# 7_-_MIO0_MIO1_SD_USB.net
KiCad netlist of a schematic drawn in Altium Designer
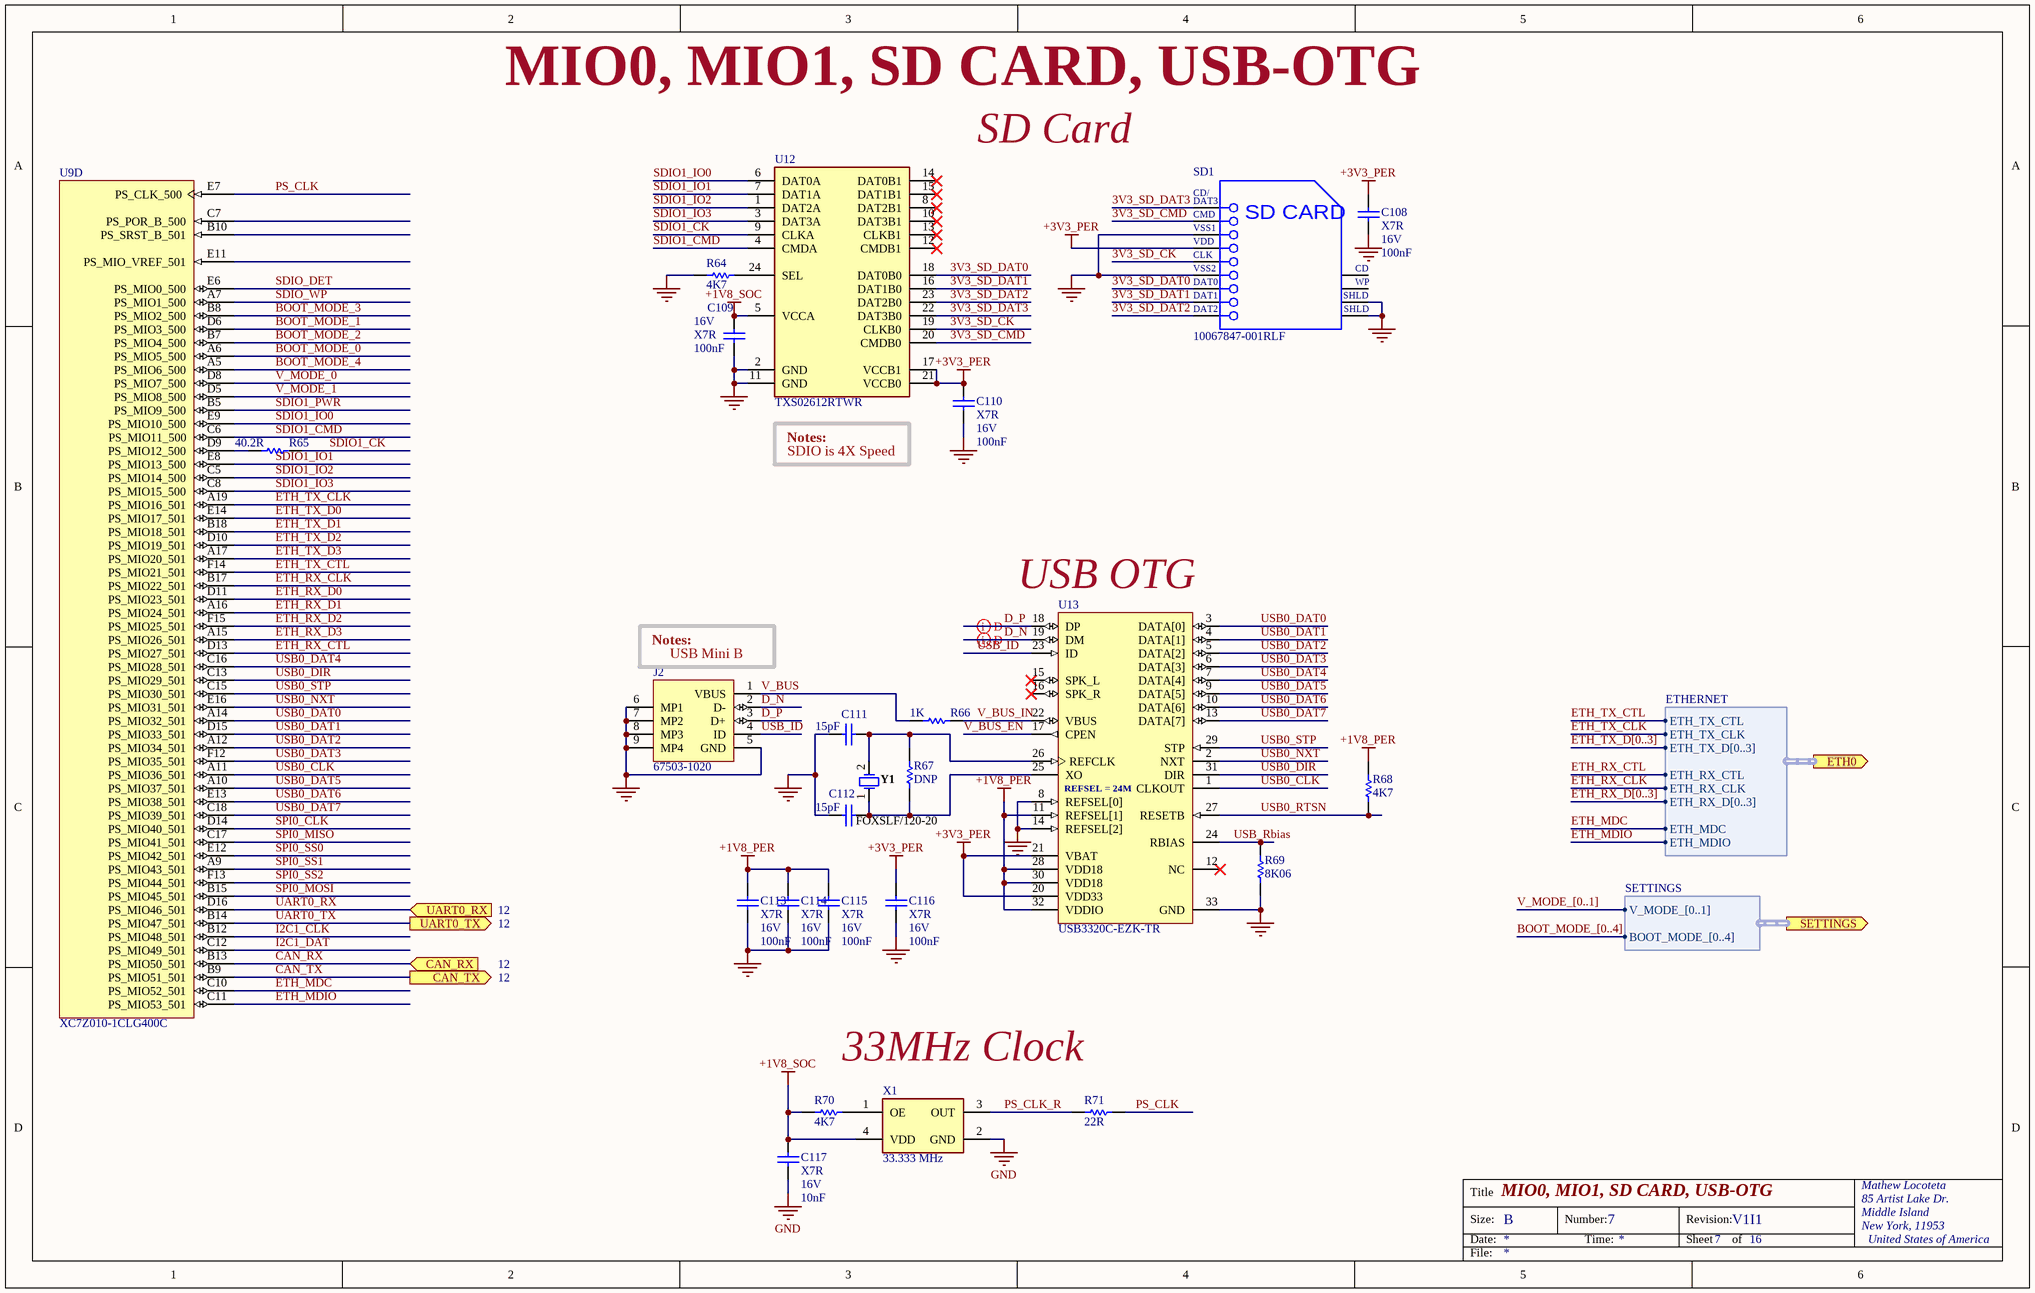
[diagram p0: [7] - MIO0, MIO1, SD, USB.SchDoc]

(export (version "E")
  (design (tool "Eeschema 10.0.6"))
  (components
    (comp (ref "C108")
      (value "100nF 0402 16V")
      (fields
        (field (name "MANUFACTURER") "KEMET")
        (field (name "MANUFACTURER PART NUMBER") "C0402C104J4RACTU")
        (field (name "TOLERANCE") "5%")
        (field (name "DIELECTRIC") "X7R")
        (field (name "VOLTAGE RATING") "16V")
        (field (name "CAPACITANCE") "100nF")
      )
      (libsource (lib "Zynq 7000") (part "C0402C104J4RACTU"))
    )
    (comp (ref "C109")
      (value "100nF 0402 16V")
      (fields
        (field (name "MANUFACTURER") "KEMET")
        (field (name "MANUFACTURER PART NUMBER") "C0402C104J4RACTU")
        (field (name "TOLERANCE") "5%")
        (field (name "DIELECTRIC") "X7R")
        (field (name "VOLTAGE RATING") "16V")
        (field (name "CAPACITANCE") "100nF")
      )
      (libsource (lib "Zynq 7000") (part "C0402C104J4RACTU"))
    )
    (comp (ref "C110")
      (value "100nF 0402 16V")
      (fields
        (field (name "MANUFACTURER") "KEMET")
        (field (name "MANUFACTURER PART NUMBER") "C0402C104J4RACTU")
        (field (name "TOLERANCE") "5%")
        (field (name "DIELECTRIC") "X7R")
        (field (name "VOLTAGE RATING") "16V")
        (field (name "CAPACITANCE") "100nF")
      )
      (libsource (lib "Zynq 7000") (part "C0402C104J4RACTU"))
    )
    (comp (ref "C111")
      (value "15 pF 50V C0G")
      (description "CAP CER 15PF 50V C0G 0402")
      (fields
        (field (name "MANUFACTURER") "TDK")
        (field (name "MANUFACTURER PART NUMBER") "CGA2B2C0G1H150J050BA")
        (field (name "CAPACITANCE") "15pF")
      )
      (libsource (lib "Zynq 7000") (part "CGA2B2C0G1H150J050BA"))
    )
    (comp (ref "C112")
      (value "15 pF 50V C0G")
      (description "CAP CER 15PF 50V C0G 0402")
      (fields
        (field (name "MANUFACTURER") "TDK")
        (field (name "MANUFACTURER PART NUMBER") "CGA2B2C0G1H150J050BA")
        (field (name "CAPACITANCE") "15pF")
      )
      (libsource (lib "Zynq 7000") (part "CGA2B2C0G1H150J050BA"))
    )
    (comp (ref "C113")
      (value "100nF 0402 16V")
      (fields
        (field (name "MANUFACTURER") "KEMET")
        (field (name "MANUFACTURER PART NUMBER") "C0402C104J4RACTU")
        (field (name "TOLERANCE") "5%")
        (field (name "DIELECTRIC") "X7R")
        (field (name "VOLTAGE RATING") "16V")
        (field (name "CAPACITANCE") "100nF")
      )
      (libsource (lib "Zynq 7000") (part "C0402C104J4RACTU"))
    )
    (comp (ref "C114")
      (value "100nF 0402 16V")
      (fields
        (field (name "MANUFACTURER") "KEMET")
        (field (name "MANUFACTURER PART NUMBER") "C0402C104J4RACTU")
        (field (name "TOLERANCE") "5%")
        (field (name "DIELECTRIC") "X7R")
        (field (name "VOLTAGE RATING") "16V")
        (field (name "CAPACITANCE") "100nF")
      )
      (libsource (lib "Zynq 7000") (part "C0402C104J4RACTU"))
    )
    (comp (ref "C115")
      (value "100nF 0402 16V")
      (fields
        (field (name "MANUFACTURER") "KEMET")
        (field (name "MANUFACTURER PART NUMBER") "C0402C104J4RACTU")
        (field (name "TOLERANCE") "5%")
        (field (name "DIELECTRIC") "X7R")
        (field (name "VOLTAGE RATING") "16V")
        (field (name "CAPACITANCE") "100nF")
      )
      (libsource (lib "Zynq 7000") (part "C0402C104J4RACTU"))
    )
    (comp (ref "C116")
      (value "100nF 0402 16V")
      (fields
        (field (name "MANUFACTURER") "KEMET")
        (field (name "MANUFACTURER PART NUMBER") "C0402C104J4RACTU")
        (field (name "TOLERANCE") "5%")
        (field (name "DIELECTRIC") "X7R")
        (field (name "VOLTAGE RATING") "16V")
        (field (name "CAPACITANCE") "100nF")
      )
      (libsource (lib "Zynq 7000") (part "C0402C104J4RACTU"))
    )
    (comp (ref "C117")
      (value "10nF 16V 0402 X7R")
      (fields
        (field (name "MANUFACTURER") "KEMET")
        (field (name "MANUFACTURER PART NUMBER") "C0402C103J4RACTU")
        (field (name "TOLERANCE") "5%")
        (field (name "DIELECTRIC") "X7R")
        (field (name "VOLTAGE RATING") "16V")
        (field (name "CAPACITANCE") "10nF")
      )
      (libsource (lib "Zynq 7000") (part "C0402C103J4RACTU"))
    )
    (comp (ref "J2")
      (value "67503-1020")
      (footprint "MOLX-67503-1020_V")
      (description "USB, MINI, SMD, RA KME04-USBMU03A01")
      (fields (field (name "MANUFACTURER") "Molex"))
      (libsource (lib "Altium Content Vault") (part "MOLX-67503-1020"))
    )
    (comp (ref "R64")
      (value "4K7 0402 1%")
      (description "Resistor SMD 4.7 kOhm 0402 PU=10000 ST, CRCW04024K70FKED, Vishay")
      (fields
        (field (name "MANUFACTURER") "Vishay")
        (field (name "MANUFACTURER PART NUMBER") "CRCW04024K70FKED")
        (field (name "RESISTANCE") "4K7")
      )
      (libsource (lib "Zynq 7000") (part "CRCW04024K70FKED"))
    )
    (comp (ref "R65")
      (value "40R2 1% 0402")
      (description "RES SMD 40.2 OHM 1% 1/16W 0402")
      (fields
        (field (name "MANUFACTURER") "Vishay")
        (field (name "MANUFACTURER PART NUMBER") "CRCW040240R2FKED")
        (field (name "RESISTANCE") "40.2R")
      )
      (libsource (lib "Zynq 7000") (part "CRCW040240R2FKED"))
    )
    (comp (ref "R66")
      (value "1K 1/8W 0402 1%")
      (description "Res Thick Film 0402 1K Ohm 1% 1/8W 100ppm/C Molded SMD SMD Paper T/R")
      (fields
        (field (name "MANUFACTURER") "Vishay Dale")
        (field (name "MANUFACTURER PART NUMBER") "CRCW04021K00FKEDHP")
        (field (name "RESISTANCE") "1K")
      )
      (libsource (lib "Zynq 7000") (part "CRCW04021K00FKEDHP"))
    )
    (comp (ref "R67")
      (value "DNP")
      (fields
        (field (name "MANUFACTURER") "Vishay")
        (field (name "MANUFACTURER PART NUMBER") "CRCW04024K70FKED")
        (field (name "TOLERANCE") "1%")
        (field (name "RESISTANCE") "DNP")
      )
      (libsource (lib "Zynq 7000") (part "CRCW04024K70FKED"))
    )
    (comp (ref "R68")
      (value "4K7 0402 1%")
      (description "Resistor SMD 4.7 kOhm 0402 PU=10000 ST, CRCW04024K70FKED, Vishay")
      (fields
        (field (name "MANUFACTURER") "Vishay")
        (field (name "MANUFACTURER PART NUMBER") "CRCW04024K70FKED")
        (field (name "RESISTANCE") "4K7")
      )
      (libsource (lib "Zynq 7000") (part "CRCW04024K70FKED"))
    )
    (comp (ref "R69")
      (value "8K06 0402 1%")
      (description "Res Thick Film 0402 8.06K Ohm 1% 0.063W(1/16W) ±100ppm/C Molded SMD Automotive Paper T/R")
      (fields
        (field (name "MANUFACTURER") "Vishay")
        (field (name "MANUFACTURER PART NUMBER") "CRCW04028K06FKED")
        (field (name "RESISTANCE") "8K06")
      )
      (libsource (lib "Zynq 7000") (part "CRCW04028K06FKED"))
    )
    (comp (ref "R70")
      (value "4K7 0402 1%")
      (description "Resistor SMD 4.7 kOhm 0402 PU=10000 ST, CRCW04024K70FKED, Vishay")
      (fields
        (field (name "MANUFACTURER") "Vishay")
        (field (name "MANUFACTURER PART NUMBER") "CRCW04024K70FKED")
        (field (name "RESISTANCE") "4K7")
      )
      (libsource (lib "Zynq 7000") (part "CRCW04024K70FKED"))
    )
    (comp (ref "R71")
      (value "22R 0402 1%")
      (description "VISHAY - CRCW040222R0FKED. - Resistor Case Style:0402 [1005 Metric]")
      (fields
        (field (name "MANUFACTURER") "Vishay")
        (field (name "MANUFACTURER PART NUMBER") "CRCW040222R0FKED")
        (field (name "RESISTANCE") "22R")
      )
      (libsource (lib "Zynq 7000") (part "CRCW040222R0FKED"))
    )
    (comp (ref "SD1")
      (value "10067847-001RLF")
      (footprint "FCI-10067847-001RLF_V")
      (description "Assembly SD Card Reader, Famale, 11 Way, -40 to 105 degC, RoHS, Tape and Reel")
      (fields (field (name "MANUFACTURER") "FCI Electronics"))
      (libsource (lib "Altium Content Vault") (part "CN-SD-9-2SW-2S"))
    )
    (comp (ref "U9")
      (value "XC7Z010-1CLG400C")
      (footprint "CLG400")
      (fields (field (name "GENERIC PART NUMBER") "XC7Z010"))
      (libsource (lib "Altium Content Vault") (part "XNLX-XC7Z010-CLG400"))
    )
    (comp (ref "U12")
      (value "TXS02612RTWR")
      (description "TEXAS INSTRUMENTS - TXS02612RTWR - SDIO EXPANDER W/VOLT TRANSLATOR, WQFN-24")
      (fields (field (name "MANUFACTURER") "Texas Instruments"))
      (libsource (lib "Zynq 7000") (part "TXS02612RTWR"))
    )
    (comp (ref "U13")
      (value "USB3320C-EZK-TR")
      (footprint "MCHP-QFN-32-5x5_V2")
      (fields (field (name "MANUFACTURER") "Microchip"))
      (libsource (lib "Altium Content Vault") (part "MCHP-USB3320-32"))
    )
    (comp (ref "X1")
      (value "33.333 MHz")
      (description "OSC MEMS 33.333MHZ CMOS SMD")
      (fields
        (field (name "MANUFACTURER") "Abracon")
        (field (name "MANUFACTURER PART NUMBER") "ASVMB-33.333MHZ-LY-T")
      )
      (libsource (lib "Zynq 7000") (part "ASVMB-33.333MHZ-LY-T"))
    )
    (comp (ref "Y1")
      (value "FOXSLF/120-20")
      (footprint "FOX-FOXSLF-2_V")
      (description "Resistance Weld Thru-Hole Crystal, 12 MHz, +/-30 ppm, -20 to 70 degC, 2-Pin THD, RoHS, Bulk")
      (libsource (lib "Altium Content Vault") (part "XTAL-1-2-2"))
    )
  )
  (nets
    (net (code "3") (name "+1V8_PER") (class "Default")
      (node (ref "C113") (pin "2") (pinfunction "2_2") (pintype "passive"))
      (node (ref "C114") (pin "2") (pinfunction "2_2") (pintype "passive"))
      (node (ref "C115") (pin "2") (pinfunction "2_2") (pintype "passive"))
      (node (ref "R68") (pin "2") (pinfunction "2_2") (pintype "passive"))
      (node (ref "U13") (pin "11") (pinfunction "REFSEL[1]_11") (pintype "input"))
      (node (ref "U13") (pin "28") (pinfunction "VDD18_28") (pintype "power_in"))
      (node (ref "U13") (pin "30") (pinfunction "VDD18_30") (pintype "power_in"))
      (node (ref "U13") (pin "32") (pinfunction "VDDIO_32") (pintype "power_in"))
    )
    (net (code "4") (name "+1V8_SOC") (class "Default")
      (node (ref "C109") (pin "2") (pinfunction "2_2") (pintype "passive"))
      (node (ref "C117") (pin "2") (pinfunction "2_2") (pintype "passive"))
      (node (ref "R70") (pin "1") (pinfunction "1_1") (pintype "passive"))
      (node (ref "U12") (pin "5") (pinfunction "VCCA_5") (pintype "passive"))
      (node (ref "X1") (pin "4") (pinfunction "VDD_4") (pintype "passive"))
    )
    (net (code "5") (name "+3V3_PER") (class "Default")
      (node (ref "C108") (pin "1") (pinfunction "1_1") (pintype "passive"))
      (node (ref "C110") (pin "1") (pinfunction "1_1") (pintype "passive"))
      (node (ref "C116") (pin "2") (pinfunction "2_2") (pintype "passive"))
      (node (ref "SD1") (pin "4") (pinfunction "VDD_4") (pintype "passive"))
      (node (ref "U12") (pin "17") (pinfunction "VCCB1_17") (pintype "passive"))
      (node (ref "U12") (pin "21") (pinfunction "VCCB0_21") (pintype "passive"))
      (node (ref "U13") (pin "20") (pinfunction "VDD33_20") (pintype "power_in"))
      (node (ref "U13") (pin "21") (pinfunction "VBAT_21") (pintype "power_in"))
    )
    (net (code "6") (name "/3V3_SD_CK") (class "Default")
      (node (ref "SD1") (pin "5") (pinfunction "CLK_5") (pintype "passive"))
      (node (ref "U12") (pin "19") (pinfunction "CLKB0_19") (pintype "passive"))
    )
    (net (code "7") (name "/3V3_SD_CMD") (class "Default")
      (node (ref "SD1") (pin "2") (pinfunction "CMD_2") (pintype "passive"))
      (node (ref "U12") (pin "20") (pinfunction "CMDB0_20") (pintype "passive"))
    )
    (net (code "8") (name "/3V3_SD_DAT0") (class "Default")
      (node (ref "SD1") (pin "7") (pinfunction "DAT0_7") (pintype "passive"))
      (node (ref "U12") (pin "18") (pinfunction "DAT0B0_18") (pintype "passive"))
    )
    (net (code "9") (name "/3V3_SD_DAT1") (class "Default")
      (node (ref "SD1") (pin "8") (pinfunction "DAT1_8") (pintype "passive"))
      (node (ref "U12") (pin "16") (pinfunction "DAT1B0_16") (pintype "passive"))
    )
    (net (code "10") (name "/3V3_SD_DAT2") (class "Default")
      (node (ref "SD1") (pin "9") (pinfunction "DAT2_9") (pintype "passive"))
      (node (ref "U12") (pin "23") (pinfunction "DAT2B0_23") (pintype "passive"))
    )
    (net (code "11") (name "/3V3_SD_DAT3") (class "Default")
      (node (ref "SD1") (pin "1") (pinfunction "CD/DAT3_1") (pintype "passive"))
      (node (ref "U12") (pin "22") (pinfunction "DAT3B0_22") (pintype "passive"))
    )
    (net (code "12") (name "/BOOT_MODE_0") (class "Default")
      (node (ref "U9") (pin "A6") (pinfunction "PS_MIO5_500_A6") (pintype "bidirectional"))
    )
    (net (code "13") (name "/BOOT_MODE_1") (class "Default")
      (node (ref "U9") (pin "D6") (pinfunction "PS_MIO3_500_D6") (pintype "bidirectional"))
    )
    (net (code "14") (name "/BOOT_MODE_2") (class "Default")
      (node (ref "U9") (pin "B7") (pinfunction "PS_MIO4_500_B7") (pintype "bidirectional"))
    )
    (net (code "15") (name "/BOOT_MODE_3") (class "Default")
      (node (ref "U9") (pin "B8") (pinfunction "PS_MIO2_500_B8") (pintype "bidirectional"))
    )
    (net (code "16") (name "/BOOT_MODE_4") (class "Default")
      (node (ref "U9") (pin "A5") (pinfunction "PS_MIO6_500_A5") (pintype "bidirectional"))
    )
    (net (code "17") (name "/CAN_RX") (class "Default")
      (node (ref "U9") (pin "B13") (pinfunction "PS_MIO50_501_B13") (pintype "bidirectional"))
    )
    (net (code "18") (name "/CAN_TX") (class "Default")
      (node (ref "U9") (pin "B9") (pinfunction "PS_MIO51_501_B9") (pintype "bidirectional"))
    )
    (net (code "19") (name "/D_N") (class "Default")
      (node (ref "J2") (pin "2") (pinfunction "D-_2") (pintype "bidirectional"))
      (node (ref "U13") (pin "19") (pinfunction "DM_19") (pintype "bidirectional"))
    )
    (net (code "20") (name "/D_P") (class "Default")
      (node (ref "J2") (pin "3") (pinfunction "D+_3") (pintype "bidirectional"))
      (node (ref "U13") (pin "18") (pinfunction "DP_18") (pintype "bidirectional"))
    )
    (net (code "22") (name "/ETH_MDC") (class "Default")
      (node (ref "U9") (pin "C10") (pinfunction "PS_MIO52_501_C10") (pintype "bidirectional"))
    )
    (net (code "23") (name "/ETH_MDIO") (class "Default")
      (node (ref "U9") (pin "C11") (pinfunction "PS_MIO53_501_C11") (pintype "bidirectional"))
    )
    (net (code "24") (name "/ETH_RX_CLK") (class "Default")
      (node (ref "U9") (pin "B17") (pinfunction "PS_MIO22_501_B17") (pintype "bidirectional"))
    )
    (net (code "25") (name "/ETH_RX_CTL") (class "Default")
      (node (ref "U9") (pin "D13") (pinfunction "PS_MIO27_501_D13") (pintype "bidirectional"))
    )
    (net (code "26") (name "/ETH_RX_D0") (class "Default")
      (node (ref "U9") (pin "D11") (pinfunction "PS_MIO23_501_D11") (pintype "bidirectional"))
    )
    (net (code "27") (name "/ETH_RX_D1") (class "Default")
      (node (ref "U9") (pin "A16") (pinfunction "PS_MIO24_501_A16") (pintype "bidirectional"))
    )
    (net (code "28") (name "/ETH_RX_D2") (class "Default")
      (node (ref "U9") (pin "F15") (pinfunction "PS_MIO25_501_F15") (pintype "bidirectional"))
    )
    (net (code "29") (name "/ETH_RX_D3") (class "Default")
      (node (ref "U9") (pin "A15") (pinfunction "PS_MIO26_501_A15") (pintype "bidirectional"))
    )
    (net (code "31") (name "/ETH_TX_CLK") (class "Default")
      (node (ref "U9") (pin "A19") (pinfunction "PS_MIO16_501_A19") (pintype "bidirectional"))
    )
    (net (code "32") (name "/ETH_TX_CTL") (class "Default")
      (node (ref "U9") (pin "F14") (pinfunction "PS_MIO21_501_F14") (pintype "bidirectional"))
    )
    (net (code "33") (name "/ETH_TX_D0") (class "Default")
      (node (ref "U9") (pin "E14") (pinfunction "PS_MIO17_501_E14") (pintype "bidirectional"))
    )
    (net (code "34") (name "/ETH_TX_D1") (class "Default")
      (node (ref "U9") (pin "B18") (pinfunction "PS_MIO18_501_B18") (pintype "bidirectional"))
    )
    (net (code "35") (name "/ETH_TX_D2") (class "Default")
      (node (ref "U9") (pin "D10") (pinfunction "PS_MIO19_501_D10") (pintype "bidirectional"))
    )
    (net (code "36") (name "/ETH_TX_D3") (class "Default")
      (node (ref "U9") (pin "A17") (pinfunction "PS_MIO20_501_A17") (pintype "bidirectional"))
    )
    (net (code "37") (name "/I2C1_CLK") (class "Default")
      (node (ref "U9") (pin "B12") (pinfunction "PS_MIO48_501_B12") (pintype "bidirectional"))
    )
    (net (code "38") (name "/I2C1_DAT") (class "Default")
      (node (ref "U9") (pin "C12") (pinfunction "PS_MIO49_501_C12") (pintype "bidirectional"))
    )
    (net (code "39") (name "/PS_CLK") (class "Default")
      (node (ref "R71") (pin "2") (pinfunction "2_2") (pintype "passive"))
      (node (ref "U9") (pin "E7") (pinfunction "PS_CLK_500_E7") (pintype "input"))
    )
    (net (code "40") (name "/PS_CLK_R") (class "Default")
      (node (ref "R71") (pin "1") (pinfunction "1_1") (pintype "passive"))
      (node (ref "X1") (pin "3") (pinfunction "OUT_3") (pintype "passive"))
    )
    (net (code "41") (name "/SDIO1_CK") (class "Default")
      (node (ref "R65") (pin "2") (pinfunction "2_2") (pintype "passive"))
      (node (ref "U12") (pin "9") (pinfunction "CLKA_9") (pintype "passive"))
    )
    (net (code "42") (name "/SDIO1_CMD") (class "Default")
      (node (ref "U12") (pin "4") (pinfunction "CMDA_4") (pintype "passive"))
      (node (ref "U9") (pin "C6") (pinfunction "PS_MIO11_500_C6") (pintype "bidirectional"))
    )
    (net (code "43") (name "/SDIO1_IO0") (class "Default")
      (node (ref "U12") (pin "6") (pinfunction "DAT0A_6") (pintype "passive"))
      (node (ref "U9") (pin "E9") (pinfunction "PS_MIO10_500_E9") (pintype "bidirectional"))
    )
    (net (code "44") (name "/SDIO1_IO1") (class "Default")
      (node (ref "U12") (pin "7") (pinfunction "DAT1A_7") (pintype "passive"))
      (node (ref "U9") (pin "E8") (pinfunction "PS_MIO13_500_E8") (pintype "bidirectional"))
    )
    (net (code "45") (name "/SDIO1_IO2") (class "Default")
      (node (ref "U12") (pin "1") (pinfunction "DAT2A_1") (pintype "passive"))
      (node (ref "U9") (pin "C5") (pinfunction "PS_MIO14_500_C5") (pintype "bidirectional"))
    )
    (net (code "46") (name "/SDIO1_IO3") (class "Default")
      (node (ref "U12") (pin "3") (pinfunction "DAT3A_3") (pintype "passive"))
      (node (ref "U9") (pin "C8") (pinfunction "PS_MIO15_500_C8") (pintype "bidirectional"))
    )
    (net (code "47") (name "/SDIO1_PWR") (class "Default")
      (node (ref "U9") (pin "B5") (pinfunction "PS_MIO9_500_B5") (pintype "bidirectional"))
    )
    (net (code "48") (name "/SDIO_DET") (class "Default")
      (node (ref "U9") (pin "E6") (pinfunction "PS_MIO0_500_E6") (pintype "bidirectional"))
    )
    (net (code "49") (name "/SDIO_WP") (class "Default")
      (node (ref "U9") (pin "A7") (pinfunction "PS_MIO1_500_A7") (pintype "bidirectional"))
    )
    (net (code "51") (name "/SPI0_CLK") (class "Default")
      (node (ref "U9") (pin "D14") (pinfunction "PS_MIO40_501_D14") (pintype "bidirectional"))
    )
    (net (code "52") (name "/SPI0_MISO") (class "Default")
      (node (ref "U9") (pin "C17") (pinfunction "PS_MIO41_501_C17") (pintype "bidirectional"))
    )
    (net (code "53") (name "/SPI0_MOSI") (class "Default")
      (node (ref "U9") (pin "B15") (pinfunction "PS_MIO45_501_B15") (pintype "bidirectional"))
    )
    (net (code "54") (name "/SPI0_SS0") (class "Default")
      (node (ref "U9") (pin "E12") (pinfunction "PS_MIO42_501_E12") (pintype "bidirectional"))
    )
    (net (code "55") (name "/SPI0_SS1") (class "Default")
      (node (ref "U9") (pin "A9") (pinfunction "PS_MIO43_501_A9") (pintype "bidirectional"))
    )
    (net (code "56") (name "/SPI0_SS2") (class "Default")
      (node (ref "U9") (pin "F13") (pinfunction "PS_MIO44_501_F13") (pintype "bidirectional"))
    )
    (net (code "57") (name "/UART0_RX") (class "Default")
      (node (ref "U9") (pin "D16") (pinfunction "PS_MIO46_501_D16") (pintype "bidirectional"))
    )
    (net (code "58") (name "/UART0_TX") (class "Default")
      (node (ref "U9") (pin "B14") (pinfunction "PS_MIO47_501_B14") (pintype "bidirectional"))
    )
    (net (code "59") (name "/USB0_CLK") (class "Default")
      (node (ref "U13") (pin "1") (pinfunction "CLKOUT_1") (pintype "tri_state"))
      (node (ref "U9") (pin "A11") (pinfunction "PS_MIO36_501_A11") (pintype "bidirectional"))
    )
    (net (code "60") (name "/USB0_DAT0") (class "Default")
      (node (ref "U13") (pin "3") (pinfunction "DATA[0]_3") (pintype "bidirectional"))
      (node (ref "U9") (pin "A14") (pinfunction "PS_MIO32_501_A14") (pintype "bidirectional"))
    )
    (net (code "61") (name "/USB0_DAT1") (class "Default")
      (node (ref "U13") (pin "4") (pinfunction "DATA[1]_4") (pintype "bidirectional"))
      (node (ref "U9") (pin "D15") (pinfunction "PS_MIO33_501_D15") (pintype "bidirectional"))
    )
    (net (code "62") (name "/USB0_DAT2") (class "Default")
      (node (ref "U13") (pin "5") (pinfunction "DATA[2]_5") (pintype "bidirectional"))
      (node (ref "U9") (pin "A12") (pinfunction "PS_MIO34_501_A12") (pintype "bidirectional"))
    )
    (net (code "63") (name "/USB0_DAT3") (class "Default")
      (node (ref "U13") (pin "6") (pinfunction "DATA[3]_6") (pintype "bidirectional"))
      (node (ref "U9") (pin "F12") (pinfunction "PS_MIO35_501_F12") (pintype "bidirectional"))
    )
    (net (code "64") (name "/USB0_DAT4") (class "Default")
      (node (ref "U13") (pin "7") (pinfunction "DATA[4]_7") (pintype "bidirectional"))
      (node (ref "U9") (pin "C16") (pinfunction "PS_MIO28_501_C16") (pintype "bidirectional"))
    )
    (net (code "65") (name "/USB0_DAT5") (class "Default")
      (node (ref "U13") (pin "9") (pinfunction "DATA[5]_9") (pintype "bidirectional"))
      (node (ref "U9") (pin "A10") (pinfunction "PS_MIO37_501_A10") (pintype "bidirectional"))
    )
    (net (code "66") (name "/USB0_DAT6") (class "Default")
      (node (ref "U13") (pin "10") (pinfunction "DATA[6]_10") (pintype "bidirectional"))
      (node (ref "U9") (pin "E13") (pinfunction "PS_MIO38_501_E13") (pintype "bidirectional"))
    )
    (net (code "67") (name "/USB0_DAT7") (class "Default")
      (node (ref "U13") (pin "13") (pinfunction "DATA[7]_13") (pintype "bidirectional"))
      (node (ref "U9") (pin "C18") (pinfunction "PS_MIO39_501_C18") (pintype "bidirectional"))
    )
    (net (code "68") (name "/USB0_DIR") (class "Default")
      (node (ref "U13") (pin "31") (pinfunction "DIR_31") (pintype "tri_state"))
      (node (ref "U9") (pin "C13") (pinfunction "PS_MIO29_501_C13") (pintype "bidirectional"))
    )
    (net (code "69") (name "/USB0_NXT") (class "Default")
      (node (ref "U13") (pin "2") (pinfunction "NXT_2") (pintype "tri_state"))
      (node (ref "U9") (pin "E16") (pinfunction "PS_MIO31_501_E16") (pintype "bidirectional"))
    )
    (net (code "70") (name "/USB0_RTSN") (class "Default")
      (node (ref "R68") (pin "1") (pinfunction "1_1") (pintype "passive"))
      (node (ref "U13") (pin "27") (pinfunction "RESETB_27") (pintype "input"))
    )
    (net (code "71") (name "/USB0_STP") (class "Default")
      (node (ref "U13") (pin "29") (pinfunction "STP_29") (pintype "input"))
      (node (ref "U9") (pin "C15") (pinfunction "PS_MIO30_501_C15") (pintype "bidirectional"))
    )
    (net (code "72") (name "/USB_ID") (class "Default")
      (node (ref "J2") (pin "4") (pinfunction "ID_4") (pintype "passive"))
      (node (ref "U13") (pin "23") (pinfunction "ID_23") (pintype "input"))
    )
    (net (code "73") (name "/USB_Rbias") (class "Default")
      (node (ref "R69") (pin "2") (pinfunction "2_2") (pintype "passive"))
      (node (ref "U13") (pin "24") (pinfunction "RBIAS_24") (pintype "passive"))
    )
    (net (code "74") (name "/V_BUS") (class "Default")
      (node (ref "J2") (pin "1") (pinfunction "VBUS_1") (pintype "power_in"))
      (node (ref "R66") (pin "1") (pinfunction "1_1") (pintype "passive"))
    )
    (net (code "75") (name "/V_BUS_EN") (class "Default")
      (node (ref "U13") (pin "17") (pinfunction "CPEN_17") (pintype "output"))
    )
    (net (code "76") (name "/V_BUS_IN") (class "Default")
      (node (ref "R66") (pin "2") (pinfunction "2_2") (pintype "passive"))
      (node (ref "U13") (pin "22") (pinfunction "VBUS_22") (pintype "bidirectional"))
    )
    (net (code "77") (name "/V_MODE_0") (class "Default")
      (node (ref "U9") (pin "D8") (pinfunction "PS_MIO7_500_D8") (pintype "bidirectional"))
    )
    (net (code "78") (name "/V_MODE_1") (class "Default")
      (node (ref "U9") (pin "D5") (pinfunction "PS_MIO8_500_D5") (pintype "bidirectional"))
    )
    (net (code "82") (name "GND") (class "Default")
      (node (ref "C108") (pin "2") (pinfunction "2_2") (pintype "passive"))
      (node (ref "C109") (pin "1") (pinfunction "1_1") (pintype "passive"))
      (node (ref "C110") (pin "2") (pinfunction "2_2") (pintype "passive"))
      (node (ref "C111") (pin "2") (pinfunction "2_2") (pintype "passive"))
      (node (ref "C112") (pin "1") (pinfunction "1_1") (pintype "passive"))
      (node (ref "C113") (pin "1") (pinfunction "1_1") (pintype "passive"))
      (node (ref "C114") (pin "1") (pinfunction "1_1") (pintype "passive"))
      (node (ref "C115") (pin "1") (pinfunction "1_1") (pintype "passive"))
      (node (ref "C116") (pin "1") (pinfunction "1_1") (pintype "passive"))
      (node (ref "C117") (pin "1") (pinfunction "1_1") (pintype "passive"))
      (node (ref "J2") (pin "5") (pinfunction "GND_5") (pintype "power_in"))
      (node (ref "J2") (pin "6") (pinfunction "MP1_6") (pintype "passive"))
      (node (ref "J2") (pin "7") (pinfunction "MP2_7") (pintype "passive"))
      (node (ref "J2") (pin "8") (pinfunction "MP3_8") (pintype "passive"))
      (node (ref "J2") (pin "9") (pinfunction "MP4_9") (pintype "passive"))
      (node (ref "R64") (pin "1") (pinfunction "1_1") (pintype "passive"))
      (node (ref "R69") (pin "1") (pinfunction "1_1") (pintype "passive"))
      (node (ref "SD1") (pin "12") (pinfunction "SHLD1_12") (pintype "passive"))
      (node (ref "SD1") (pin "13") (pinfunction "SHLD2_13") (pintype "passive"))
      (node (ref "SD1") (pin "3") (pinfunction "VSS1_3") (pintype "passive"))
      (node (ref "SD1") (pin "6") (pinfunction "VSS2_6") (pintype "passive"))
      (node (ref "U12") (pin "11") (pinfunction "GND_11") (pintype "passive"))
      (node (ref "U12") (pin "2") (pinfunction "GND_2") (pintype "passive"))
      (node (ref "U13") (pin "14") (pinfunction "REFSEL[2]_14") (pintype "input"))
      (node (ref "U13") (pin "33") (pinfunction "GND_33") (pintype "power_in"))
      (node (ref "U13") (pin "8") (pinfunction "REFSEL[0]_8") (pintype "input"))
      (node (ref "X1") (pin "2") (pinfunction "GND_2") (pintype "passive"))
    )
    (net (code "83") (name "Net-(U9D-PS_MIO12_500)") (class "Default")
      (node (ref "R65") (pin "1") (pinfunction "1_1") (pintype "passive"))
      (node (ref "U9") (pin "D9") (pinfunction "PS_MIO12_500_D9") (pintype "bidirectional"))
    )
    (net (code "84") (name "Net-(U12-SEL)") (class "Default")
      (node (ref "R64") (pin "2") (pinfunction "2_2") (pintype "passive"))
      (node (ref "U12") (pin "24") (pinfunction "SEL_24") (pintype "passive"))
    )
    (net (code "85") (name "Net-(U13-REFCLK)") (class "Default")
      (node (ref "C111") (pin "1") (pinfunction "1_1") (pintype "passive"))
      (node (ref "R67") (pin "2") (pinfunction "2_2") (pintype "passive"))
      (node (ref "U13") (pin "26") (pinfunction "REFCLK_26") (pintype "input"))
      (node (ref "Y1") (pin "2") (pinfunction "2_2") (pintype "passive"))
    )
    (net (code "86") (name "Net-(U13-XO)") (class "Default")
      (node (ref "C112") (pin "2") (pinfunction "2_2") (pintype "passive"))
      (node (ref "R67") (pin "1") (pinfunction "1_1") (pintype "passive"))
      (node (ref "U13") (pin "25") (pinfunction "XO_25") (pintype "passive"))
      (node (ref "Y1") (pin "1") (pinfunction "1_1") (pintype "passive"))
    )
    (net (code "87") (name "Net-(X1-OE)") (class "Default")
      (node (ref "R70") (pin "2") (pinfunction "2_2") (pintype "passive"))
      (node (ref "X1") (pin "1") (pinfunction "OE_1") (pintype "passive"))
    )
    (net (code "88") (name "unconnected-(SD1-CD-Pad10)") (class "Default")
      (node (ref "SD1") (pin "10") (pinfunction "CD_10") (pintype "passive"))
    )
    (net (code "89") (name "unconnected-(SD1-WP-Pad11)") (class "Default")
      (node (ref "SD1") (pin "11") (pinfunction "WP_11") (pintype "passive"))
    )
    (net (code "90") (name "unconnected-(U9D-PS_MIO_VREF_501-PadE11)") (class "Default")
      (node (ref "U9") (pin "E11") (pinfunction "PS_MIO_VREF_501_E11") (pintype "input"))
    )
    (net (code "91") (name "unconnected-(U9D-PS_POR_B_500-PadC7)") (class "Default")
      (node (ref "U9") (pin "C7") (pinfunction "PS_POR_B_500_C7") (pintype "input"))
    )
    (net (code "92") (name "unconnected-(U9D-PS_SRST_B_501-PadB10)") (class "Default")
      (node (ref "U9") (pin "B10") (pinfunction "PS_SRST_B_501_B10") (pintype "input"))
    )
    (net (code "93") (name "unconnected-(U12-CLKB1-Pad13)") (class "Default")
      (node (ref "U12") (pin "13") (pinfunction "CLKB1_13") (pintype "passive+no_connect"))
    )
    (net (code "94") (name "unconnected-(U12-CMDB1-Pad12)") (class "Default")
      (node (ref "U12") (pin "12") (pinfunction "CMDB1_12") (pintype "passive+no_connect"))
    )
    (net (code "95") (name "unconnected-(U12-DAT0B1-Pad14)") (class "Default")
      (node (ref "U12") (pin "14") (pinfunction "DAT0B1_14") (pintype "passive+no_connect"))
    )
    (net (code "96") (name "unconnected-(U12-DAT1B1-Pad15)") (class "Default")
      (node (ref "U12") (pin "15") (pinfunction "DAT1B1_15") (pintype "passive+no_connect"))
    )
    (net (code "97") (name "unconnected-(U12-DAT2B1-Pad8)") (class "Default")
      (node (ref "U12") (pin "8") (pinfunction "DAT2B1_8") (pintype "passive+no_connect"))
    )
    (net (code "98") (name "unconnected-(U12-DAT3B1-Pad10)") (class "Default")
      (node (ref "U12") (pin "10") (pinfunction "DAT3B1_10") (pintype "passive+no_connect"))
    )
    (net (code "99") (name "unconnected-(U13-NC-Pad12)") (class "Default")
      (node (ref "U13") (pin "12") (pinfunction "NC_12") (pintype "passive+no_connect"))
    )
    (net (code "100") (name "unconnected-(U13-SPK_L-Pad15)") (class "Default")
      (node (ref "U13") (pin "15") (pinfunction "SPK_L_15") (pintype "bidirectional+no_connect"))
    )
    (net (code "101") (name "unconnected-(U13-SPK_R-Pad16)") (class "Default")
      (node (ref "U13") (pin "16") (pinfunction "SPK_R_16") (pintype "bidirectional+no_connect"))
    )
  )
)
